# pwr.net
KiCad netlist of a schematic drawn in Altium Designer
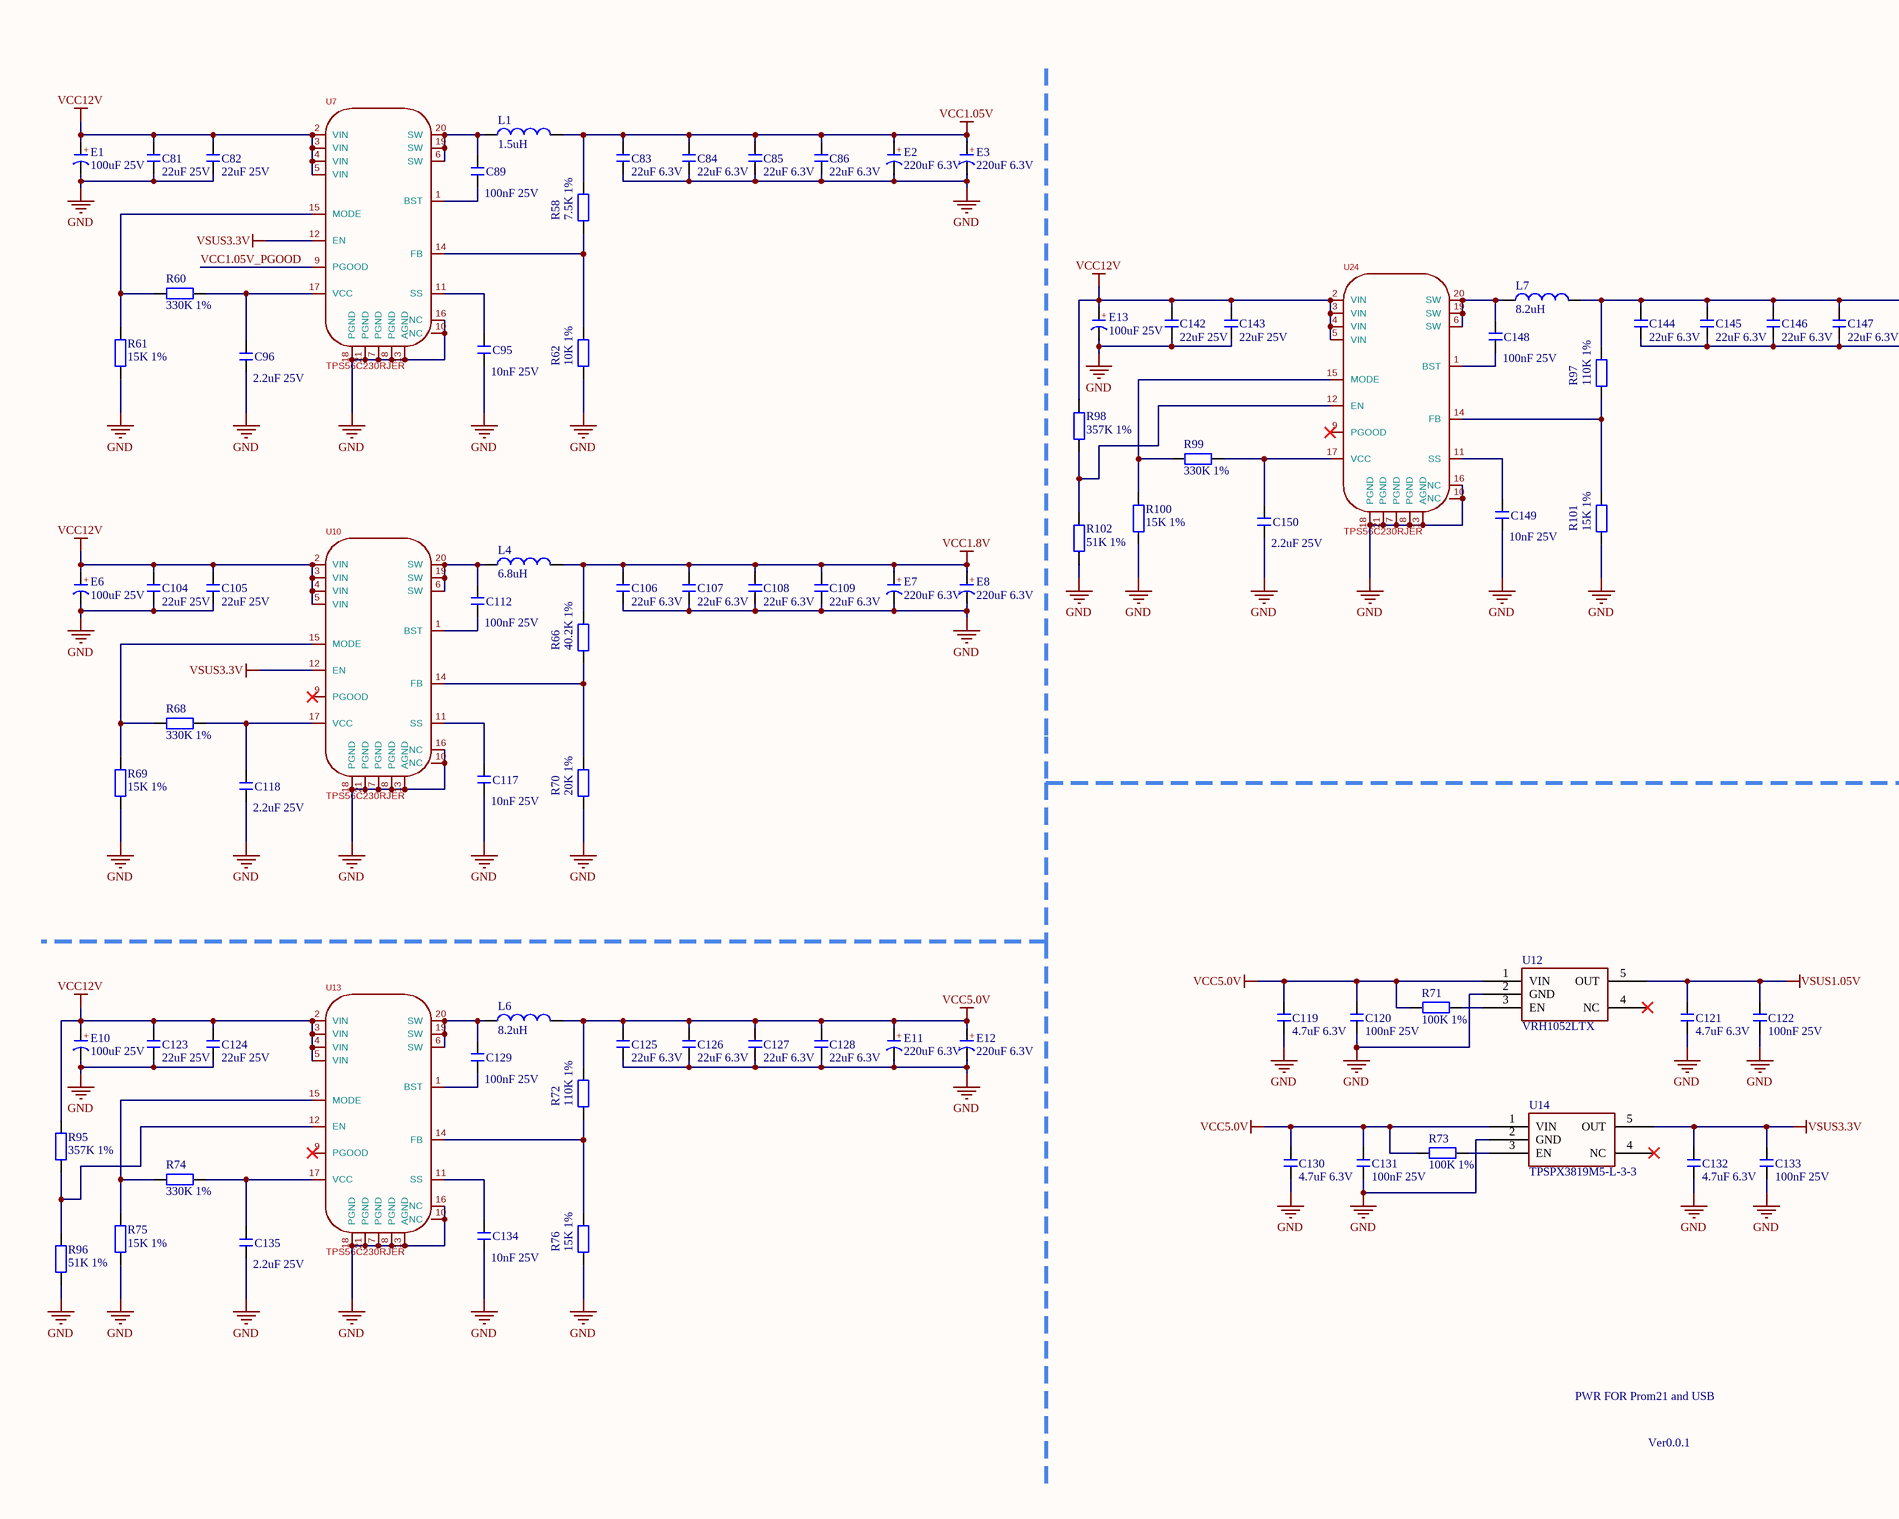
[diagram p0: pwr.SchDoc, left]
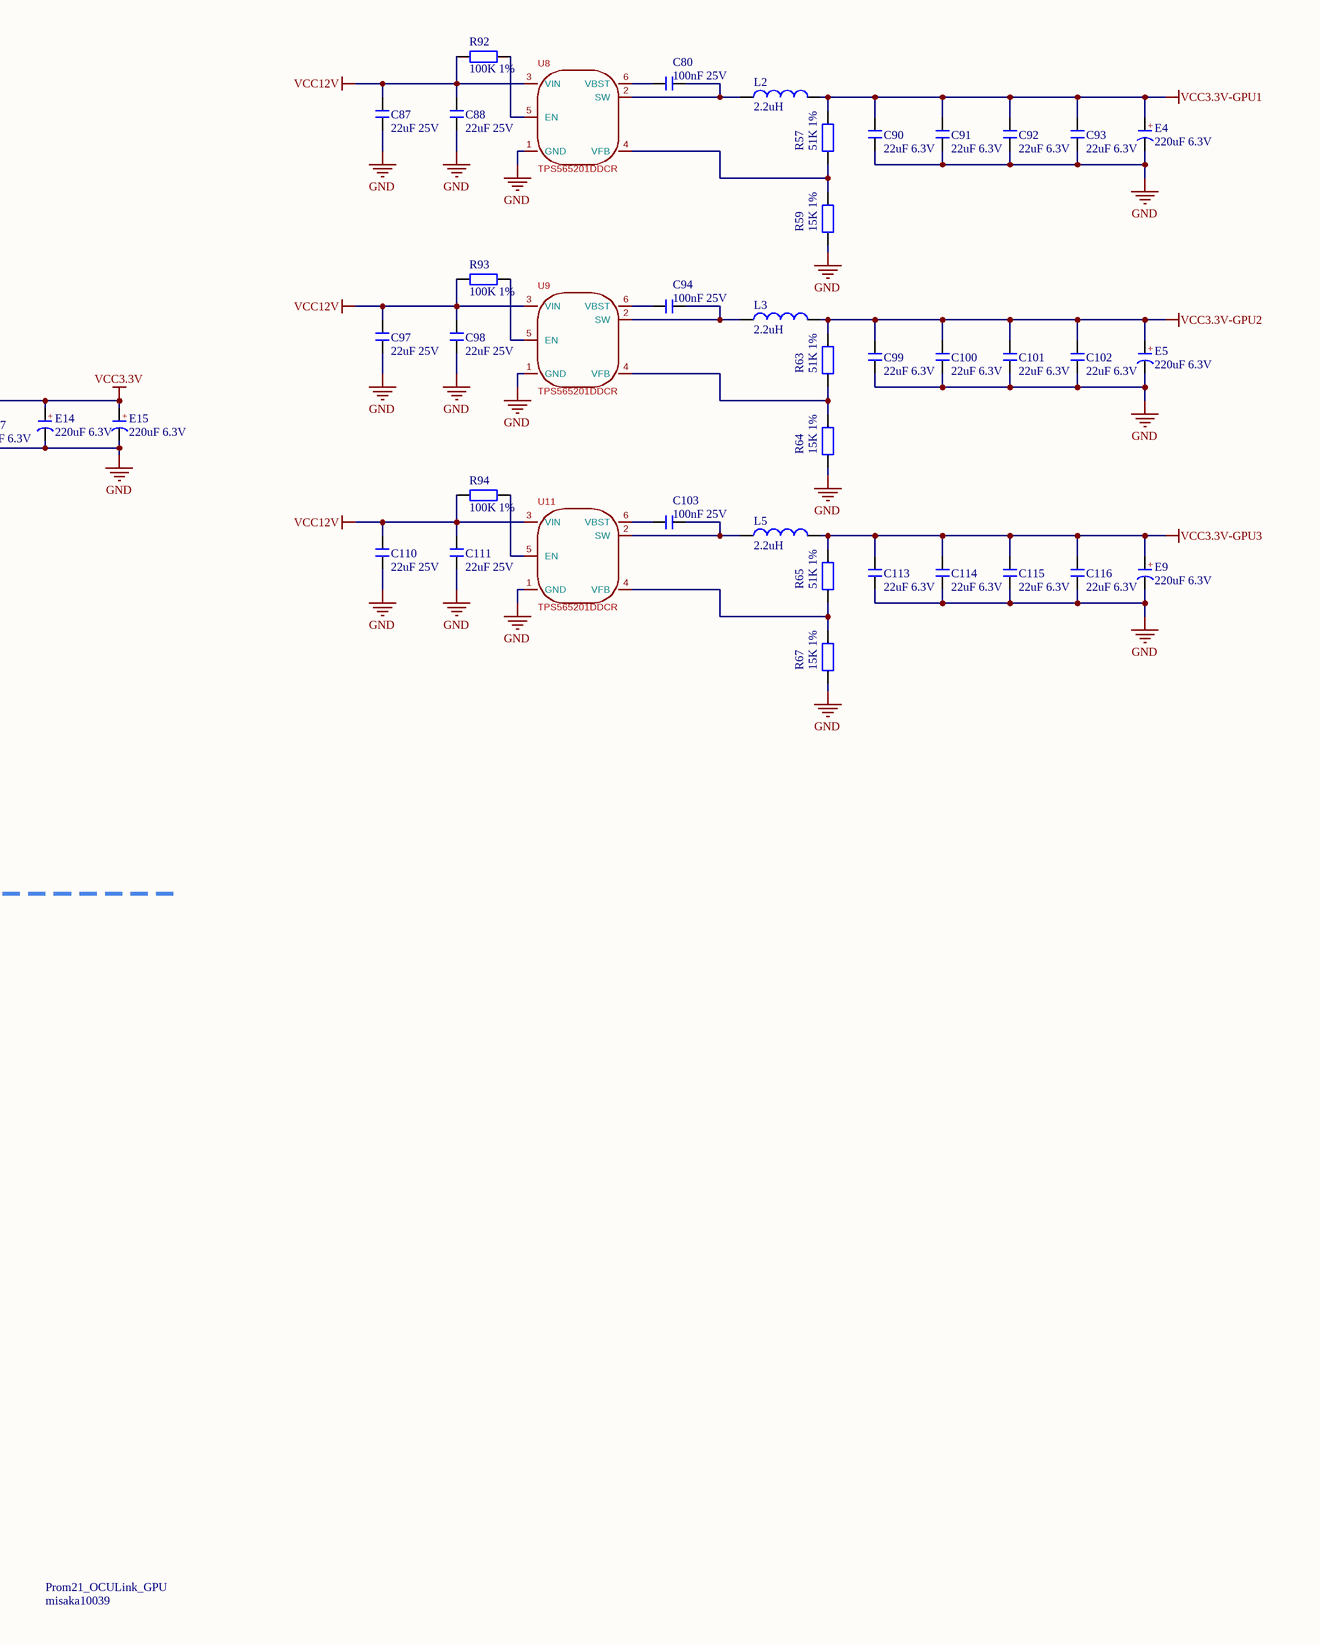
[diagram p1: pwr.SchDoc, right]

(export (version "E")
  (design (tool "Eeschema 10.0.6"))
  (components
    (comp (ref "C80")
      (value "100nF 25V")
      (footprint "C0402_L")
      (description "无极性贴片电容")
      (libsource (lib "Capacitor") (part "C"))
    )
    (comp (ref "C81")
      (value "22uF 25V")
      (footprint "C0805_L")
      (description "无极性贴片电容")
      (libsource (lib "Capacitor") (part "C"))
    )
    (comp (ref "C82")
      (value "22uF 25V")
      (footprint "C0805_L")
      (description "无极性贴片电容")
      (libsource (lib "Capacitor") (part "C"))
    )
    (comp (ref "C83")
      (value "22uF 6.3V")
      (footprint "C0603_L")
      (description "无极性贴片电容")
      (libsource (lib "Capacitor") (part "C"))
    )
    (comp (ref "C84")
      (value "22uF 6.3V")
      (footprint "C0603_L")
      (description "无极性贴片电容")
      (libsource (lib "Capacitor") (part "C"))
    )
    (comp (ref "C85")
      (value "22uF 6.3V")
      (footprint "C0603_L")
      (description "无极性贴片电容")
      (libsource (lib "Capacitor") (part "C"))
    )
    (comp (ref "C86")
      (value "22uF 6.3V")
      (footprint "C0603_L")
      (description "无极性贴片电容")
      (libsource (lib "Capacitor") (part "C"))
    )
    (comp (ref "C87")
      (value "22uF 25V")
      (footprint "C0805_L")
      (description "无极性贴片电容")
      (libsource (lib "Capacitor") (part "C"))
    )
    (comp (ref "C88")
      (value "22uF 25V")
      (footprint "C0805_L")
      (description "无极性贴片电容")
      (libsource (lib "Capacitor") (part "C"))
    )
    (comp (ref "C89")
      (value "100nF 25V")
      (footprint "C0402_L")
      (description "无极性贴片电容")
      (libsource (lib "Capacitor") (part "C"))
    )
    (comp (ref "C90")
      (value "22uF 6.3V")
      (footprint "C0603_L")
      (description "无极性贴片电容")
      (libsource (lib "Capacitor") (part "C"))
    )
    (comp (ref "C91")
      (value "22uF 6.3V")
      (footprint "C0603_L")
      (description "无极性贴片电容")
      (libsource (lib "Capacitor") (part "C"))
    )
    (comp (ref "C92")
      (value "22uF 6.3V")
      (footprint "C0603_L")
      (description "无极性贴片电容")
      (libsource (lib "Capacitor") (part "C"))
    )
    (comp (ref "C93")
      (value "22uF 6.3V")
      (footprint "C0603_L")
      (description "无极性贴片电容")
      (libsource (lib "Capacitor") (part "C"))
    )
    (comp (ref "C94")
      (value "100nF 25V")
      (footprint "C0402_L")
      (description "无极性贴片电容")
      (libsource (lib "Capacitor") (part "C"))
    )
    (comp (ref "C95")
      (value "10nF 25V")
      (footprint "C0402_L")
      (description "无极性贴片电容")
      (libsource (lib "Capacitor") (part "C"))
    )
    (comp (ref "C96")
      (value "2.2uF 25V")
      (footprint "C0402_L")
      (description "无极性贴片电容")
      (libsource (lib "Capacitor") (part "C"))
    )
    (comp (ref "C97")
      (value "22uF 25V")
      (footprint "C0805_L")
      (description "无极性贴片电容")
      (libsource (lib "Capacitor") (part "C"))
    )
    (comp (ref "C98")
      (value "22uF 25V")
      (footprint "C0805_L")
      (description "无极性贴片电容")
      (libsource (lib "Capacitor") (part "C"))
    )
    (comp (ref "C99")
      (value "22uF 6.3V")
      (footprint "C0603_L")
      (description "无极性贴片电容")
      (libsource (lib "Capacitor") (part "C"))
    )
    (comp (ref "C100")
      (value "22uF 6.3V")
      (footprint "C0603_L")
      (description "无极性贴片电容")
      (libsource (lib "Capacitor") (part "C"))
    )
    (comp (ref "C101")
      (value "22uF 6.3V")
      (footprint "C0603_L")
      (description "无极性贴片电容")
      (libsource (lib "Capacitor") (part "C"))
    )
    (comp (ref "C102")
      (value "22uF 6.3V")
      (footprint "C0603_L")
      (description "无极性贴片电容")
      (libsource (lib "Capacitor") (part "C"))
    )
    (comp (ref "C103")
      (value "100nF 25V")
      (footprint "C0402_L")
      (description "无极性贴片电容")
      (libsource (lib "Capacitor") (part "C"))
    )
    (comp (ref "C104")
      (value "22uF 25V")
      (footprint "C0805_L")
      (description "无极性贴片电容")
      (libsource (lib "Capacitor") (part "C"))
    )
    (comp (ref "C105")
      (value "22uF 25V")
      (footprint "C0805_L")
      (description "无极性贴片电容")
      (libsource (lib "Capacitor") (part "C"))
    )
    (comp (ref "C106")
      (value "22uF 6.3V")
      (footprint "C0603_L")
      (description "无极性贴片电容")
      (libsource (lib "Capacitor") (part "C"))
    )
    (comp (ref "C107")
      (value "22uF 6.3V")
      (footprint "C0603_L")
      (description "无极性贴片电容")
      (libsource (lib "Capacitor") (part "C"))
    )
    (comp (ref "C108")
      (value "22uF 6.3V")
      (footprint "C0603_L")
      (description "无极性贴片电容")
      (libsource (lib "Capacitor") (part "C"))
    )
    (comp (ref "C109")
      (value "22uF 6.3V")
      (footprint "C0603_L")
      (description "无极性贴片电容")
      (libsource (lib "Capacitor") (part "C"))
    )
    (comp (ref "C110")
      (value "22uF 25V")
      (footprint "C0805_L")
      (description "无极性贴片电容")
      (libsource (lib "Capacitor") (part "C"))
    )
    (comp (ref "C111")
      (value "22uF 25V")
      (footprint "C0805_L")
      (description "无极性贴片电容")
      (libsource (lib "Capacitor") (part "C"))
    )
    (comp (ref "C112")
      (value "100nF 25V")
      (footprint "C0402_L")
      (description "无极性贴片电容")
      (libsource (lib "Capacitor") (part "C"))
    )
    (comp (ref "C113")
      (value "22uF 6.3V")
      (footprint "C0603_L")
      (description "无极性贴片电容")
      (libsource (lib "Capacitor") (part "C"))
    )
    (comp (ref "C114")
      (value "22uF 6.3V")
      (footprint "C0603_L")
      (description "无极性贴片电容")
      (libsource (lib "Capacitor") (part "C"))
    )
    (comp (ref "C115")
      (value "22uF 6.3V")
      (footprint "C0603_L")
      (description "无极性贴片电容")
      (libsource (lib "Capacitor") (part "C"))
    )
    (comp (ref "C116")
      (value "22uF 6.3V")
      (footprint "C0603_L")
      (description "无极性贴片电容")
      (libsource (lib "Capacitor") (part "C"))
    )
    (comp (ref "C117")
      (value "10nF 25V")
      (footprint "C0402_L")
      (description "无极性贴片电容")
      (libsource (lib "Capacitor") (part "C"))
    )
    (comp (ref "C118")
      (value "2.2uF 25V")
      (footprint "C0402_L")
      (description "无极性贴片电容")
      (libsource (lib "Capacitor") (part "C"))
    )
    (comp (ref "C119")
      (value "4.7uF 6.3V")
      (footprint "C0402_L")
      (description "无极性贴片电容")
      (libsource (lib "Capacitor") (part "C"))
    )
    (comp (ref "C120")
      (value "100nF 25V")
      (footprint "C0402_L")
      (description "无极性贴片电容")
      (libsource (lib "Capacitor") (part "C"))
    )
    (comp (ref "C121")
      (value "4.7uF 6.3V")
      (footprint "C0402_L")
      (description "无极性贴片电容")
      (libsource (lib "Capacitor") (part "C"))
    )
    (comp (ref "C122")
      (value "100nF 25V")
      (footprint "C0402_L")
      (description "无极性贴片电容")
      (libsource (lib "Capacitor") (part "C"))
    )
    (comp (ref "C123")
      (value "22uF 25V")
      (footprint "C0805_L")
      (description "无极性贴片电容")
      (libsource (lib "Capacitor") (part "C"))
    )
    (comp (ref "C124")
      (value "22uF 25V")
      (footprint "C0805_L")
      (description "无极性贴片电容")
      (libsource (lib "Capacitor") (part "C"))
    )
    (comp (ref "C125")
      (value "22uF 6.3V")
      (footprint "C0603_L")
      (description "无极性贴片电容")
      (libsource (lib "Capacitor") (part "C"))
    )
    (comp (ref "C126")
      (value "22uF 6.3V")
      (footprint "C0603_L")
      (description "无极性贴片电容")
      (libsource (lib "Capacitor") (part "C"))
    )
    (comp (ref "C127")
      (value "22uF 6.3V")
      (footprint "C0603_L")
      (description "无极性贴片电容")
      (libsource (lib "Capacitor") (part "C"))
    )
    (comp (ref "C128")
      (value "22uF 6.3V")
      (footprint "C0603_L")
      (description "无极性贴片电容")
      (libsource (lib "Capacitor") (part "C"))
    )
    (comp (ref "C129")
      (value "100nF 25V")
      (footprint "C0402_L")
      (description "无极性贴片电容")
      (libsource (lib "Capacitor") (part "C"))
    )
    (comp (ref "C130")
      (value "4.7uF 6.3V")
      (footprint "C0402_L")
      (description "无极性贴片电容")
      (libsource (lib "Capacitor") (part "C"))
    )
    (comp (ref "C131")
      (value "100nF 25V")
      (footprint "C0402_L")
      (description "无极性贴片电容")
      (libsource (lib "Capacitor") (part "C"))
    )
    (comp (ref "C132")
      (value "4.7uF 6.3V")
      (footprint "C0402_L")
      (description "无极性贴片电容")
      (libsource (lib "Capacitor") (part "C"))
    )
    (comp (ref "C133")
      (value "100nF 25V")
      (footprint "C0402_L")
      (description "无极性贴片电容")
      (libsource (lib "Capacitor") (part "C"))
    )
    (comp (ref "C134")
      (value "10nF 25V")
      (footprint "C0402_L")
      (description "无极性贴片电容")
      (libsource (lib "Capacitor") (part "C"))
    )
    (comp (ref "C135")
      (value "2.2uF 25V")
      (footprint "C0402_L")
      (description "无极性贴片电容")
      (libsource (lib "Capacitor") (part "C"))
    )
    (comp (ref "C142")
      (value "22uF 25V")
      (footprint "C0805_L")
      (description "无极性贴片电容")
      (libsource (lib "Capacitor") (part "C"))
    )
    (comp (ref "C143")
      (value "22uF 25V")
      (footprint "C0805_L")
      (description "无极性贴片电容")
      (libsource (lib "Capacitor") (part "C"))
    )
    (comp (ref "C144")
      (value "22uF 6.3V")
      (footprint "C0603_L")
      (description "无极性贴片电容")
      (libsource (lib "Capacitor") (part "C"))
    )
    (comp (ref "C145")
      (value "22uF 6.3V")
      (footprint "C0603_L")
      (description "无极性贴片电容")
      (libsource (lib "Capacitor") (part "C"))
    )
    (comp (ref "C146")
      (value "22uF 6.3V")
      (footprint "C0603_L")
      (description "无极性贴片电容")
      (libsource (lib "Capacitor") (part "C"))
    )
    (comp (ref "C147")
      (value "22uF 6.3V")
      (footprint "C0603_L")
      (description "无极性贴片电容")
      (libsource (lib "Capacitor") (part "C"))
    )
    (comp (ref "C148")
      (value "100nF 25V")
      (footprint "C0402_L")
      (description "无极性贴片电容")
      (libsource (lib "Capacitor") (part "C"))
    )
    (comp (ref "C149")
      (value "10nF 25V")
      (footprint "C0402_L")
      (description "无极性贴片电容")
      (libsource (lib "Capacitor") (part "C"))
    )
    (comp (ref "C150")
      (value "2.2uF 25V")
      (footprint "C0402_L")
      (description "无极性贴片电容")
      (libsource (lib "Capacitor") (part "C"))
    )
    (comp (ref "E1")
      (value "100uF 25V")
      (footprint "CT 6*4 - R")
      (description "贴片电解电容")
      (libsource (lib "Capacitor") (part "C-CAP"))
    )
    (comp (ref "E2")
      (value "220uF 6.3V")
      (footprint "CT 6*4 - C")
      (description "贴片电解电容")
      (libsource (lib "Capacitor") (part "C-CAP"))
    )
    (comp (ref "E3")
      (value "220uF 6.3V")
      (footprint "CT 6*4 - C")
      (description "贴片电解电容")
      (libsource (lib "Capacitor") (part "C-CAP"))
    )
    (comp (ref "E4")
      (value "220uF 6.3V")
      (footprint "CT 6*4 - C")
      (description "贴片电解电容")
      (libsource (lib "Capacitor") (part "C-CAP"))
    )
    (comp (ref "E5")
      (value "220uF 6.3V")
      (footprint "CT 6*4 - C")
      (description "贴片电解电容")
      (libsource (lib "Capacitor") (part "C-CAP"))
    )
    (comp (ref "E6")
      (value "100uF 25V")
      (footprint "CT 6*4 - R")
      (description "贴片电解电容")
      (libsource (lib "Capacitor") (part "C-CAP"))
    )
    (comp (ref "E7")
      (value "220uF 6.3V")
      (footprint "CT 6*4 - C")
      (description "贴片电解电容")
      (libsource (lib "Capacitor") (part "C-CAP"))
    )
    (comp (ref "E8")
      (value "220uF 6.3V")
      (footprint "CT 6*4 - C")
      (description "贴片电解电容")
      (libsource (lib "Capacitor") (part "C-CAP"))
    )
    (comp (ref "E9")
      (value "220uF 6.3V")
      (footprint "CT 6*4 - C")
      (description "贴片电解电容")
      (libsource (lib "Capacitor") (part "C-CAP"))
    )
    (comp (ref "E10")
      (value "100uF 25V")
      (footprint "CT 6*4 - R")
      (description "贴片电解电容")
      (libsource (lib "Capacitor") (part "C-CAP"))
    )
    (comp (ref "E11")
      (value "220uF 6.3V")
      (footprint "CT 6*4 - C")
      (description "贴片电解电容")
      (libsource (lib "Capacitor") (part "C-CAP"))
    )
    (comp (ref "E12")
      (value "220uF 6.3V")
      (footprint "CT 6*4 - C")
      (description "贴片电解电容")
      (libsource (lib "Capacitor") (part "C-CAP"))
    )
    (comp (ref "E13")
      (value "100uF 25V")
      (footprint "CT 6*4 - R")
      (description "贴片电解电容")
      (libsource (lib "Capacitor") (part "C-CAP"))
    )
    (comp (ref "E14")
      (value "220uF 6.3V")
      (footprint "CT 6*4 - C")
      (description "贴片电解电容")
      (libsource (lib "Capacitor") (part "C-CAP"))
    )
    (comp (ref "E15")
      (value "220uF 6.3V")
      (footprint "CT 6*4 - C")
      (description "贴片电解电容")
      (libsource (lib "Capacitor") (part "C-CAP"))
    )
    (comp (ref "L1")
      (value "1.5uH")
      (footprint "L0630贴片电感")
      (description "小功率贴片电感")
      (libsource (lib "Inductor") (part "L"))
    )
    (comp (ref "L2")
      (value "2.2uH")
      (footprint "L0630贴片电感")
      (description "小功率贴片电感")
      (libsource (lib "Inductor") (part "L"))
    )
    (comp (ref "L3")
      (value "2.2uH")
      (footprint "L0630贴片电感")
      (description "小功率贴片电感")
      (libsource (lib "Inductor") (part "L"))
    )
    (comp (ref "L4")
      (value "6.8uH")
      (footprint "L0630贴片电感")
      (description "小功率贴片电感")
      (libsource (lib "Inductor") (part "L"))
    )
    (comp (ref "L5")
      (value "2.2uH")
      (footprint "L0630贴片电感")
      (description "小功率贴片电感")
      (libsource (lib "Inductor") (part "L"))
    )
    (comp (ref "L6")
      (value "8.2uH")
      (footprint "L0630贴片电感")
      (description "小功率贴片电感")
      (libsource (lib "Inductor") (part "L"))
    )
    (comp (ref "L7")
      (value "8.2uH")
      (footprint "L0630贴片电感")
      (description "小功率贴片电感")
      (libsource (lib "Inductor") (part "L"))
    )
    (comp (ref "R57")
      (value "51K 1%")
      (footprint "R0402_L")
      (description "贴片电阻")
      (libsource (lib "Resistor") (part "R"))
    )
    (comp (ref "R58")
      (value "7.5K 1%")
      (footprint "R0402_L")
      (description "贴片电阻")
      (libsource (lib "Resistor") (part "R"))
    )
    (comp (ref "R59")
      (value "15K 1%")
      (footprint "R0402_L")
      (description "贴片电阻")
      (libsource (lib "Resistor") (part "R"))
    )
    (comp (ref "R60")
      (value "330K 1%")
      (footprint "R0402_L")
      (description "贴片电阻")
      (libsource (lib "Resistor") (part "R"))
    )
    (comp (ref "R61")
      (value "15K 1%")
      (footprint "R0402_L")
      (description "贴片电阻")
      (libsource (lib "Resistor") (part "R"))
    )
    (comp (ref "R62")
      (value "10K 1%")
      (footprint "R0402_L")
      (description "贴片电阻")
      (libsource (lib "Resistor") (part "R"))
    )
    (comp (ref "R63")
      (value "51K 1%")
      (footprint "R0402_L")
      (description "贴片电阻")
      (libsource (lib "Resistor") (part "R"))
    )
    (comp (ref "R64")
      (value "15K 1%")
      (footprint "R0402_L")
      (description "贴片电阻")
      (libsource (lib "Resistor") (part "R"))
    )
    (comp (ref "R65")
      (value "51K 1%")
      (footprint "R0402_L")
      (description "贴片电阻")
      (libsource (lib "Resistor") (part "R"))
    )
    (comp (ref "R66")
      (value "40.2K 1%")
      (footprint "R0402_L")
      (description "贴片电阻")
      (libsource (lib "Resistor") (part "R"))
    )
    (comp (ref "R67")
      (value "15K 1%")
      (footprint "R0402_L")
      (description "贴片电阻")
      (libsource (lib "Resistor") (part "R"))
    )
    (comp (ref "R68")
      (value "330K 1%")
      (footprint "R0402_L")
      (description "贴片电阻")
      (libsource (lib "Resistor") (part "R"))
    )
    (comp (ref "R69")
      (value "15K 1%")
      (footprint "R0402_L")
      (description "贴片电阻")
      (libsource (lib "Resistor") (part "R"))
    )
    (comp (ref "R70")
      (value "20K 1%")
      (footprint "R0402_L")
      (description "贴片电阻")
      (libsource (lib "Resistor") (part "R"))
    )
    (comp (ref "R71")
      (value "100K 1%")
      (footprint "R0402_L")
      (description "贴片电阻")
      (libsource (lib "Resistor") (part "R"))
    )
    (comp (ref "R72")
      (value "110K 1%")
      (footprint "R0402_L")
      (description "贴片电阻")
      (libsource (lib "Resistor") (part "R"))
    )
    (comp (ref "R73")
      (value "100K 1%")
      (footprint "R0402_L")
      (description "贴片电阻")
      (libsource (lib "Resistor") (part "R"))
    )
    (comp (ref "R74")
      (value "330K 1%")
      (footprint "R0402_L")
      (description "贴片电阻")
      (libsource (lib "Resistor") (part "R"))
    )
    (comp (ref "R75")
      (value "15K 1%")
      (footprint "R0402_L")
      (description "贴片电阻")
      (libsource (lib "Resistor") (part "R"))
    )
    (comp (ref "R76")
      (value "15K 1%")
      (footprint "R0402_L")
      (description "贴片电阻")
      (libsource (lib "Resistor") (part "R"))
    )
    (comp (ref "R92")
      (value "100K 1%")
      (footprint "R0402_L")
      (description "贴片电阻")
      (libsource (lib "Resistor") (part "R"))
    )
    (comp (ref "R93")
      (value "100K 1%")
      (footprint "R0402_L")
      (description "贴片电阻")
      (libsource (lib "Resistor") (part "R"))
    )
    (comp (ref "R94")
      (value "100K 1%")
      (footprint "R0402_L")
      (description "贴片电阻")
      (libsource (lib "Resistor") (part "R"))
    )
    (comp (ref "R95")
      (value "357K 1%")
      (footprint "R0402_L")
      (description "贴片电阻")
      (libsource (lib "Resistor") (part "R"))
    )
    (comp (ref "R96")
      (value "51K 1%")
      (footprint "R0402_L")
      (description "贴片电阻")
      (libsource (lib "Resistor") (part "R"))
    )
    (comp (ref "R97")
      (value "110K 1%")
      (footprint "R0402_L")
      (description "贴片电阻")
      (libsource (lib "Resistor") (part "R"))
    )
    (comp (ref "R98")
      (value "357K 1%")
      (footprint "R0402_L")
      (description "贴片电阻")
      (libsource (lib "Resistor") (part "R"))
    )
    (comp (ref "R99")
      (value "330K 1%")
      (footprint "R0402_L")
      (description "贴片电阻")
      (libsource (lib "Resistor") (part "R"))
    )
    (comp (ref "R100")
      (value "15K 1%")
      (footprint "R0402_L")
      (description "贴片电阻")
      (libsource (lib "Resistor") (part "R"))
    )
    (comp (ref "R101")
      (value "15K 1%")
      (footprint "R0402_L")
      (description "贴片电阻")
      (libsource (lib "Resistor") (part "R"))
    )
    (comp (ref "R102")
      (value "51K 1%")
      (footprint "R0402_L")
      (description "贴片电阻")
      (libsource (lib "Resistor") (part "R"))
    )
    (comp (ref "U7")
      (value "TPS56C230RJER")
      (footprint "VQFN-20_L3.0-W3.0-P0.45-TL-EP_TI_RJE")
      (description "功能类型:降压型;输出类型:可调;输入电压:4.5V~18V;输出电压:600mV~5.5V;输出电流(最大值):12A;")
      (fields (field (name "MANUFACTURER") "TI(德州仪器)"))
      (libsource (lib "DCDC Convert") (part "TPS56C230RJER"))
    )
    (comp (ref "U8")
      (value "TPS565201DDCR")
      (footprint "SOT23-6L")
      (description "功能类型:降压型;输出类型:可调;输入电压:4.5V~17V;输出电压:600mV~7V;输出电流(最大值):5A;")
      (fields (field (name "MANUFACTURER") "TI(德州仪器)"))
      (libsource (lib "DCDC Convert") (part "TPS565201DDCR"))
    )
    (comp (ref "U9")
      (value "TPS565201DDCR")
      (footprint "SOT23-6L")
      (description "功能类型:降压型;输出类型:可调;输入电压:4.5V~17V;输出电压:600mV~7V;输出电流(最大值):5A;")
      (fields (field (name "MANUFACTURER") "TI(德州仪器)"))
      (libsource (lib "DCDC Convert") (part "TPS565201DDCR"))
    )
    (comp (ref "U10")
      (value "TPS56C230RJER")
      (footprint "VQFN-20_L3.0-W3.0-P0.45-TL-EP_TI_RJE")
      (description "功能类型:降压型;输出类型:可调;输入电压:4.5V~18V;输出电压:600mV~5.5V;输出电流(最大值):12A;")
      (fields (field (name "MANUFACTURER") "TI(德州仪器)"))
      (libsource (lib "DCDC Convert") (part "TPS56C230RJER"))
    )
    (comp (ref "U11")
      (value "TPS565201DDCR")
      (footprint "SOT23-6L")
      (description "功能类型:降压型;输出类型:可调;输入电压:4.5V~17V;输出电压:600mV~7V;输出电流(最大值):5A;")
      (fields (field (name "MANUFACTURER") "TI(德州仪器)"))
      (libsource (lib "DCDC Convert") (part "TPS565201DDCR"))
    )
    (comp (ref "U12")
      (value "VRH1052LTX")
      (footprint "SOT23-5L")
      (description "SOT-23-5")
      (libsource (lib "LDO") (part "LP5907_MFX"))
    )
    (comp (ref "U13")
      (value "TPS56C230RJER")
      (footprint "VQFN-20_L3.0-W3.0-P0.45-TL-EP_TI_RJE")
      (description "功能类型:降压型;输出类型:可调;输入电压:4.5V~18V;输出电压:600mV~5.5V;输出电流(最大值):12A;")
      (fields (field (name "MANUFACTURER") "TI(德州仪器)"))
      (libsource (lib "DCDC Convert") (part "TPS56C230RJER"))
    )
    (comp (ref "U14")
      (value "TPSPX3819M5-L-3-3")
      (footprint "SOT23-5L")
      (description "SOT-23-5")
      (libsource (lib "LDO") (part "LP5907_MFX"))
    )
    (comp (ref "U24")
      (value "TPS56C230RJER")
      (footprint "VQFN-20_L3.0-W3.0-P0.45-TL-EP_TI_RJE")
      (description "功能类型:降压型;输出类型:可调;输入电压:4.5V~18V;输出电压:600mV~5.5V;输出电流(最大值):12A;")
      (fields (field (name "MANUFACTURER") "TI(德州仪器)"))
      (libsource (lib "DCDC Convert") (part "TPS56C230RJER"))
    )
  )
  (nets
    (net (code "1") (name "/VCC1.05V_PGOOD") (class "Default")
      (node (ref "U7") (pin "9") (pinfunction "PGOOD_9") (pintype "passive"))
    )
    (net (code "2") (name "GND") (class "Default")
      (node (ref "C100") (pin "1") (pinfunction "1_1") (pintype "passive"))
      (node (ref "C101") (pin "1") (pinfunction "1_1") (pintype "passive"))
      (node (ref "C102") (pin "1") (pinfunction "1_1") (pintype "passive"))
      (node (ref "C104") (pin "1") (pinfunction "1_1") (pintype "passive"))
      (node (ref "C105") (pin "1") (pinfunction "1_1") (pintype "passive"))
      (node (ref "C106") (pin "1") (pinfunction "1_1") (pintype "passive"))
      (node (ref "C107") (pin "1") (pinfunction "1_1") (pintype "passive"))
      (node (ref "C108") (pin "1") (pinfunction "1_1") (pintype "passive"))
      (node (ref "C109") (pin "1") (pinfunction "1_1") (pintype "passive"))
      (node (ref "C110") (pin "1") (pinfunction "1_1") (pintype "passive"))
      (node (ref "C111") (pin "1") (pinfunction "1_1") (pintype "passive"))
      (node (ref "C113") (pin "1") (pinfunction "1_1") (pintype "passive"))
      (node (ref "C114") (pin "1") (pinfunction "1_1") (pintype "passive"))
      (node (ref "C115") (pin "1") (pinfunction "1_1") (pintype "passive"))
      (node (ref "C116") (pin "1") (pinfunction "1_1") (pintype "passive"))
      (node (ref "C117") (pin "1") (pinfunction "1_1") (pintype "passive"))
      (node (ref "C118") (pin "1") (pinfunction "1_1") (pintype "passive"))
      (node (ref "C119") (pin "1") (pinfunction "1_1") (pintype "passive"))
      (node (ref "C120") (pin "2") (pinfunction "2_2") (pintype "passive"))
      (node (ref "C121") (pin "1") (pinfunction "1_1") (pintype "passive"))
      (node (ref "C122") (pin "2") (pinfunction "2_2") (pintype "passive"))
      (node (ref "C123") (pin "1") (pinfunction "1_1") (pintype "passive"))
      (node (ref "C124") (pin "1") (pinfunction "1_1") (pintype "passive"))
      (node (ref "C125") (pin "1") (pinfunction "1_1") (pintype "passive"))
      (node (ref "C126") (pin "1") (pinfunction "1_1") (pintype "passive"))
      (node (ref "C127") (pin "1") (pinfunction "1_1") (pintype "passive"))
      (node (ref "C128") (pin "1") (pinfunction "1_1") (pintype "passive"))
      (node (ref "C130") (pin "1") (pinfunction "1_1") (pintype "passive"))
      (node (ref "C131") (pin "2") (pinfunction "2_2") (pintype "passive"))
      (node (ref "C132") (pin "1") (pinfunction "1_1") (pintype "passive"))
      (node (ref "C133") (pin "2") (pinfunction "2_2") (pintype "passive"))
      (node (ref "C134") (pin "1") (pinfunction "1_1") (pintype "passive"))
      (node (ref "C135") (pin "1") (pinfunction "1_1") (pintype "passive"))
      (node (ref "C142") (pin "1") (pinfunction "1_1") (pintype "passive"))
      (node (ref "C143") (pin "1") (pinfunction "1_1") (pintype "passive"))
      (node (ref "C144") (pin "1") (pinfunction "1_1") (pintype "passive"))
      (node (ref "C145") (pin "1") (pinfunction "1_1") (pintype "passive"))
      (node (ref "C146") (pin "1") (pinfunction "1_1") (pintype "passive"))
      (node (ref "C147") (pin "1") (pinfunction "1_1") (pintype "passive"))
      (node (ref "C149") (pin "1") (pinfunction "1_1") (pintype "passive"))
      (node (ref "C150") (pin "1") (pinfunction "1_1") (pintype "passive"))
      (node (ref "C81") (pin "1") (pinfunction "1_1") (pintype "passive"))
      (node (ref "C82") (pin "1") (pinfunction "1_1") (pintype "passive"))
      (node (ref "C83") (pin "1") (pinfunction "1_1") (pintype "passive"))
      (node (ref "C84") (pin "1") (pinfunction "1_1") (pintype "passive"))
      (node (ref "C85") (pin "1") (pinfunction "1_1") (pintype "passive"))
      (node (ref "C86") (pin "1") (pinfunction "1_1") (pintype "passive"))
      (node (ref "C87") (pin "1") (pinfunction "1_1") (pintype "passive"))
      (node (ref "C88") (pin "1") (pinfunction "1_1") (pintype "passive"))
      (node (ref "C90") (pin "1") (pinfunction "1_1") (pintype "passive"))
      (node (ref "C91") (pin "1") (pinfunction "1_1") (pintype "passive"))
      (node (ref "C92") (pin "1") (pinfunction "1_1") (pintype "passive"))
      (node (ref "C93") (pin "1") (pinfunction "1_1") (pintype "passive"))
      (node (ref "C95") (pin "1") (pinfunction "1_1") (pintype "passive"))
      (node (ref "C96") (pin "1") (pinfunction "1_1") (pintype "passive"))
      (node (ref "C97") (pin "1") (pinfunction "1_1") (pintype "passive"))
      (node (ref "C98") (pin "1") (pinfunction "1_1") (pintype "passive"))
      (node (ref "C99") (pin "1") (pinfunction "1_1") (pintype "passive"))
      (node (ref "E1") (pin "2") (pinfunction "K_2") (pintype "passive"))
      (node (ref "E10") (pin "2") (pinfunction "K_2") (pintype "passive"))
      (node (ref "E11") (pin "2") (pinfunction "K_2") (pintype "passive"))
      (node (ref "E12") (pin "2") (pinfunction "K_2") (pintype "passive"))
      (node (ref "E13") (pin "2") (pinfunction "K_2") (pintype "passive"))
      (node (ref "E14") (pin "2") (pinfunction "K_2") (pintype "passive"))
      (node (ref "E15") (pin "2") (pinfunction "K_2") (pintype "passive"))
      (node (ref "E2") (pin "2") (pinfunction "K_2") (pintype "passive"))
      (node (ref "E3") (pin "2") (pinfunction "K_2") (pintype "passive"))
      (node (ref "E4") (pin "2") (pinfunction "K_2") (pintype "passive"))
      (node (ref "E5") (pin "2") (pinfunction "K_2") (pintype "passive"))
      (node (ref "E6") (pin "2") (pinfunction "K_2") (pintype "passive"))
      (node (ref "E7") (pin "2") (pinfunction "K_2") (pintype "passive"))
      (node (ref "E8") (pin "2") (pinfunction "K_2") (pintype "passive"))
      (node (ref "E9") (pin "2") (pinfunction "K_2") (pintype "passive"))
      (node (ref "R100") (pin "1") (pinfunction "1_1") (pintype "passive"))
      (node (ref "R101") (pin "2") (pinfunction "2_2") (pintype "passive"))
      (node (ref "R102") (pin "1") (pinfunction "1_1") (pintype "passive"))
      (node (ref "R59") (pin "2") (pinfunction "2_2") (pintype "passive"))
      (node (ref "R61") (pin "1") (pinfunction "1_1") (pintype "passive"))
      (node (ref "R62") (pin "2") (pinfunction "2_2") (pintype "passive"))
      (node (ref "R64") (pin "2") (pinfunction "2_2") (pintype "passive"))
      (node (ref "R67") (pin "2") (pinfunction "2_2") (pintype "passive"))
      (node (ref "R69") (pin "1") (pinfunction "1_1") (pintype "passive"))
      (node (ref "R70") (pin "2") (pinfunction "2_2") (pintype "passive"))
      (node (ref "R75") (pin "1") (pinfunction "1_1") (pintype "passive"))
      (node (ref "R76") (pin "2") (pinfunction "2_2") (pintype "passive"))
      (node (ref "R96") (pin "1") (pinfunction "1_1") (pintype "passive"))
      (node (ref "U10") (pin "10") (pinfunction "NC_10") (pintype "passive"))
      (node (ref "U10") (pin "13") (pinfunction "AGND_13") (pintype "passive"))
      (node (ref "U10") (pin "16") (pinfunction "NC_16") (pintype "passive"))
      (node (ref "U10") (pin "18") (pinfunction "PGND_18") (pintype "passive"))
      (node (ref "U10") (pin "21") (pinfunction "PGND_21") (pintype "passive"))
      (node (ref "U10") (pin "7") (pinfunction "PGND_7") (pintype "passive"))
      (node (ref "U10") (pin "8") (pinfunction "PGND_8") (pintype "passive"))
      (node (ref "U11") (pin "1") (pinfunction "GND_1") (pintype "passive"))
      (node (ref "U12") (pin "2") (pinfunction "GND_2") (pintype "passive"))
      (node (ref "U13") (pin "10") (pinfunction "NC_10") (pintype "passive"))
      (node (ref "U13") (pin "13") (pinfunction "AGND_13") (pintype "passive"))
      (node (ref "U13") (pin "16") (pinfunction "NC_16") (pintype "passive"))
      (node (ref "U13") (pin "18") (pinfunction "PGND_18") (pintype "passive"))
      (node (ref "U13") (pin "21") (pinfunction "PGND_21") (pintype "passive"))
      (node (ref "U13") (pin "7") (pinfunction "PGND_7") (pintype "passive"))
      (node (ref "U13") (pin "8") (pinfunction "PGND_8") (pintype "passive"))
      (node (ref "U14") (pin "2") (pinfunction "GND_2") (pintype "passive"))
      (node (ref "U24") (pin "10") (pinfunction "NC_10") (pintype "passive"))
      (node (ref "U24") (pin "13") (pinfunction "AGND_13") (pintype "passive"))
      (node (ref "U24") (pin "16") (pinfunction "NC_16") (pintype "passive"))
      (node (ref "U24") (pin "18") (pinfunction "PGND_18") (pintype "passive"))
      (node (ref "U24") (pin "21") (pinfunction "PGND_21") (pintype "passive"))
      (node (ref "U24") (pin "7") (pinfunction "PGND_7") (pintype "passive"))
      (node (ref "U24") (pin "8") (pinfunction "PGND_8") (pintype "passive"))
      (node (ref "U7") (pin "10") (pinfunction "NC_10") (pintype "passive"))
      (node (ref "U7") (pin "13") (pinfunction "AGND_13") (pintype "passive"))
      (node (ref "U7") (pin "16") (pinfunction "NC_16") (pintype "passive"))
      (node (ref "U7") (pin "18") (pinfunction "PGND_18") (pintype "passive"))
      (node (ref "U7") (pin "21") (pinfunction "PGND_21") (pintype "passive"))
      (node (ref "U7") (pin "7") (pinfunction "PGND_7") (pintype "passive"))
      (node (ref "U7") (pin "8") (pinfunction "PGND_8") (pintype "passive"))
      (node (ref "U8") (pin "1") (pinfunction "GND_1") (pintype "passive"))
      (node (ref "U9") (pin "1") (pinfunction "GND_1") (pintype "passive"))
    )
    (net (code "3") (name "Net-(C89-Pad2)") (class "Default")
      (node (ref "C89") (pin "2") (pinfunction "2_2") (pintype "passive"))
      (node (ref "L1") (pin "1") (pinfunction "1_1") (pintype "passive"))
      (node (ref "U7") (pin "19") (pinfunction "SW_19") (pintype "passive"))
      (node (ref "U7") (pin "20") (pinfunction "SW_20") (pintype "passive"))
      (node (ref "U7") (pin "6") (pinfunction "SW_6") (pintype "passive"))
    )
    (net (code "4") (name "Net-(C112-Pad2)") (class "Default")
      (node (ref "C112") (pin "2") (pinfunction "2_2") (pintype "passive"))
      (node (ref "L4") (pin "1") (pinfunction "1_1") (pintype "passive"))
      (node (ref "U10") (pin "19") (pinfunction "SW_19") (pintype "passive"))
      (node (ref "U10") (pin "20") (pinfunction "SW_20") (pintype "passive"))
      (node (ref "U10") (pin "6") (pinfunction "SW_6") (pintype "passive"))
    )
    (net (code "5") (name "Net-(C129-Pad2)") (class "Default")
      (node (ref "C129") (pin "2") (pinfunction "2_2") (pintype "passive"))
      (node (ref "L6") (pin "1") (pinfunction "1_1") (pintype "passive"))
      (node (ref "U13") (pin "19") (pinfunction "SW_19") (pintype "passive"))
      (node (ref "U13") (pin "20") (pinfunction "SW_20") (pintype "passive"))
      (node (ref "U13") (pin "6") (pinfunction "SW_6") (pintype "passive"))
    )
    (net (code "6") (name "Net-(C148-Pad2)") (class "Default")
      (node (ref "C148") (pin "2") (pinfunction "2_2") (pintype "passive"))
      (node (ref "L7") (pin "1") (pinfunction "1_1") (pintype "passive"))
      (node (ref "U24") (pin "19") (pinfunction "SW_19") (pintype "passive"))
      (node (ref "U24") (pin "20") (pinfunction "SW_20") (pintype "passive"))
      (node (ref "U24") (pin "6") (pinfunction "SW_6") (pintype "passive"))
    )
    (net (code "7") (name "Net-(U7-BST)") (class "Default")
      (node (ref "C89") (pin "1") (pinfunction "1_1") (pintype "passive"))
      (node (ref "U7") (pin "1") (pinfunction "BST_1") (pintype "passive"))
    )
    (net (code "8") (name "Net-(U7-FB)") (class "Default")
      (node (ref "R58") (pin "2") (pinfunction "2_2") (pintype "passive"))
      (node (ref "R62") (pin "1") (pinfunction "1_1") (pintype "passive"))
      (node (ref "U7") (pin "14") (pinfunction "FB_14") (pintype "passive"))
    )
    (net (code "9") (name "Net-(U7-MODE)") (class "Default")
      (node (ref "R60") (pin "2") (pinfunction "2_2") (pintype "passive"))
      (node (ref "R61") (pin "2") (pinfunction "2_2") (pintype "passive"))
      (node (ref "U7") (pin "15") (pinfunction "MODE_15") (pintype "passive"))
    )
    (net (code "10") (name "Net-(U7-SS)") (class "Default")
      (node (ref "C95") (pin "2") (pinfunction "2_2") (pintype "passive"))
      (node (ref "U7") (pin "11") (pinfunction "SS_11") (pintype "passive"))
    )
    (net (code "11") (name "Net-(U7-VCC)") (class "Default")
      (node (ref "C96") (pin "2") (pinfunction "2_2") (pintype "passive"))
      (node (ref "R60") (pin "1") (pinfunction "1_1") (pintype "passive"))
      (node (ref "U7") (pin "17") (pinfunction "VCC_17") (pintype "passive"))
    )
    (net (code "12") (name "Net-(U8-EN)") (class "Default")
      (node (ref "R92") (pin "2") (pinfunction "2_2") (pintype "passive"))
      (node (ref "U8") (pin "5") (pinfunction "EN_5") (pintype "passive"))
    )
    (net (code "13") (name "Net-(U8-SW)") (class "Default")
      (node (ref "C80") (pin "1") (pinfunction "1_1") (pintype "passive"))
      (node (ref "L2") (pin "1") (pinfunction "1_1") (pintype "passive"))
      (node (ref "U8") (pin "2") (pinfunction "SW_2") (pintype "passive"))
    )
    (net (code "14") (name "Net-(U8-VBST)") (class "Default")
      (node (ref "C80") (pin "2") (pinfunction "2_2") (pintype "passive"))
      (node (ref "U8") (pin "6") (pinfunction "VBST_6") (pintype "passive"))
    )
    (net (code "15") (name "Net-(U8-VFB)") (class "Default")
      (node (ref "R57") (pin "2") (pinfunction "2_2") (pintype "passive"))
      (node (ref "R59") (pin "1") (pinfunction "1_1") (pintype "passive"))
      (node (ref "U8") (pin "4") (pinfunction "VFB_4") (pintype "passive"))
    )
    (net (code "16") (name "Net-(U9-EN)") (class "Default")
      (node (ref "R93") (pin "2") (pinfunction "2_2") (pintype "passive"))
      (node (ref "U9") (pin "5") (pinfunction "EN_5") (pintype "passive"))
    )
    (net (code "17") (name "Net-(U9-SW)") (class "Default")
      (node (ref "C94") (pin "1") (pinfunction "1_1") (pintype "passive"))
      (node (ref "L3") (pin "1") (pinfunction "1_1") (pintype "passive"))
      (node (ref "U9") (pin "2") (pinfunction "SW_2") (pintype "passive"))
    )
    (net (code "18") (name "Net-(U9-VBST)") (class "Default")
      (node (ref "C94") (pin "2") (pinfunction "2_2") (pintype "passive"))
      (node (ref "U9") (pin "6") (pinfunction "VBST_6") (pintype "passive"))
    )
    (net (code "19") (name "Net-(U9-VFB)") (class "Default")
      (node (ref "R63") (pin "2") (pinfunction "2_2") (pintype "passive"))
      (node (ref "R64") (pin "1") (pinfunction "1_1") (pintype "passive"))
      (node (ref "U9") (pin "4") (pinfunction "VFB_4") (pintype "passive"))
    )
    (net (code "20") (name "Net-(U10-BST)") (class "Default")
      (node (ref "C112") (pin "1") (pinfunction "1_1") (pintype "passive"))
      (node (ref "U10") (pin "1") (pinfunction "BST_1") (pintype "passive"))
    )
    (net (code "21") (name "Net-(U10-FB)") (class "Default")
      (node (ref "R66") (pin "2") (pinfunction "2_2") (pintype "passive"))
      (node (ref "R70") (pin "1") (pinfunction "1_1") (pintype "passive"))
      (node (ref "U10") (pin "14") (pinfunction "FB_14") (pintype "passive"))
    )
    (net (code "22") (name "Net-(U10-MODE)") (class "Default")
      (node (ref "R68") (pin "2") (pinfunction "2_2") (pintype "passive"))
      (node (ref "R69") (pin "2") (pinfunction "2_2") (pintype "passive"))
      (node (ref "U10") (pin "15") (pinfunction "MODE_15") (pintype "passive"))
    )
    (net (code "23") (name "Net-(U10-SS)") (class "Default")
      (node (ref "C117") (pin "2") (pinfunction "2_2") (pintype "passive"))
      (node (ref "U10") (pin "11") (pinfunction "SS_11") (pintype "passive"))
    )
    (net (code "24") (name "Net-(U10-VCC)") (class "Default")
      (node (ref "C118") (pin "2") (pinfunction "2_2") (pintype "passive"))
      (node (ref "R68") (pin "1") (pinfunction "1_1") (pintype "passive"))
      (node (ref "U10") (pin "17") (pinfunction "VCC_17") (pintype "passive"))
    )
    (net (code "25") (name "Net-(U11-EN)") (class "Default")
      (node (ref "R94") (pin "2") (pinfunction "2_2") (pintype "passive"))
      (node (ref "U11") (pin "5") (pinfunction "EN_5") (pintype "passive"))
    )
    (net (code "26") (name "Net-(U11-SW)") (class "Default")
      (node (ref "C103") (pin "1") (pinfunction "1_1") (pintype "passive"))
      (node (ref "L5") (pin "1") (pinfunction "1_1") (pintype "passive"))
      (node (ref "U11") (pin "2") (pinfunction "SW_2") (pintype "passive"))
    )
    (net (code "27") (name "Net-(U11-VBST)") (class "Default")
      (node (ref "C103") (pin "2") (pinfunction "2_2") (pintype "passive"))
      (node (ref "U11") (pin "6") (pinfunction "VBST_6") (pintype "passive"))
    )
    (net (code "28") (name "Net-(U11-VFB)") (class "Default")
      (node (ref "R65") (pin "2") (pinfunction "2_2") (pintype "passive"))
      (node (ref "R67") (pin "1") (pinfunction "1_1") (pintype "passive"))
      (node (ref "U11") (pin "4") (pinfunction "VFB_4") (pintype "passive"))
    )
    (net (code "29") (name "Net-(U12-EN)") (class "Default")
      (node (ref "R71") (pin "1") (pinfunction "1_1") (pintype "passive"))
      (node (ref "U12") (pin "3") (pinfunction "EN_3") (pintype "passive"))
    )
    (net (code "30") (name "Net-(U13-BST)") (class "Default")
      (node (ref "C129") (pin "1") (pinfunction "1_1") (pintype "passive"))
      (node (ref "U13") (pin "1") (pinfunction "BST_1") (pintype "passive"))
    )
    (net (code "31") (name "Net-(U13-EN)") (class "Default")
      (node (ref "R95") (pin "1") (pinfunction "1_1") (pintype "passive"))
      (node (ref "R96") (pin "2") (pinfunction "2_2") (pintype "passive"))
      (node (ref "U13") (pin "12") (pinfunction "EN_12") (pintype "passive"))
    )
    (net (code "32") (name "Net-(U13-FB)") (class "Default")
      (node (ref "R72") (pin "2") (pinfunction "2_2") (pintype "passive"))
      (node (ref "R76") (pin "1") (pinfunction "1_1") (pintype "passive"))
      (node (ref "U13") (pin "14") (pinfunction "FB_14") (pintype "passive"))
    )
    (net (code "33") (name "Net-(U13-MODE)") (class "Default")
      (node (ref "R74") (pin "2") (pinfunction "2_2") (pintype "passive"))
      (node (ref "R75") (pin "2") (pinfunction "2_2") (pintype "passive"))
      (node (ref "U13") (pin "15") (pinfunction "MODE_15") (pintype "passive"))
    )
    (net (code "34") (name "Net-(U13-SS)") (class "Default")
      (node (ref "C134") (pin "2") (pinfunction "2_2") (pintype "passive"))
      (node (ref "U13") (pin "11") (pinfunction "SS_11") (pintype "passive"))
    )
    (net (code "35") (name "Net-(U13-VCC)") (class "Default")
      (node (ref "C135") (pin "2") (pinfunction "2_2") (pintype "passive"))
      (node (ref "R74") (pin "1") (pinfunction "1_1") (pintype "passive"))
      (node (ref "U13") (pin "17") (pinfunction "VCC_17") (pintype "passive"))
    )
    (net (code "36") (name "Net-(U14-EN)") (class "Default")
      (node (ref "R73") (pin "1") (pinfunction "1_1") (pintype "passive"))
      (node (ref "U14") (pin "3") (pinfunction "EN_3") (pintype "passive"))
    )
    (net (code "37") (name "Net-(U24-BST)") (class "Default")
      (node (ref "C148") (pin "1") (pinfunction "1_1") (pintype "passive"))
      (node (ref "U24") (pin "1") (pinfunction "BST_1") (pintype "passive"))
    )
    (net (code "38") (name "Net-(U24-EN)") (class "Default")
      (node (ref "R102") (pin "2") (pinfunction "2_2") (pintype "passive"))
      (node (ref "R98") (pin "1") (pinfunction "1_1") (pintype "passive"))
      (node (ref "U24") (pin "12") (pinfunction "EN_12") (pintype "passive"))
    )
    (net (code "39") (name "Net-(U24-FB)") (class "Default")
      (node (ref "R101") (pin "1") (pinfunction "1_1") (pintype "passive"))
      (node (ref "R97") (pin "2") (pinfunction "2_2") (pintype "passive"))
      (node (ref "U24") (pin "14") (pinfunction "FB_14") (pintype "passive"))
    )
    (net (code "40") (name "Net-(U24-MODE)") (class "Default")
      (node (ref "R100") (pin "2") (pinfunction "2_2") (pintype "passive"))
      (node (ref "R99") (pin "2") (pinfunction "2_2") (pintype "passive"))
      (node (ref "U24") (pin "15") (pinfunction "MODE_15") (pintype "passive"))
    )
    (net (code "41") (name "Net-(U24-SS)") (class "Default")
      (node (ref "C149") (pin "2") (pinfunction "2_2") (pintype "passive"))
      (node (ref "U24") (pin "11") (pinfunction "SS_11") (pintype "passive"))
    )
    (net (code "42") (name "Net-(U24-VCC)") (class "Default")
      (node (ref "C150") (pin "2") (pinfunction "2_2") (pintype "passive"))
      (node (ref "R99") (pin "1") (pinfunction "1_1") (pintype "passive"))
      (node (ref "U24") (pin "17") (pinfunction "VCC_17") (pintype "passive"))
    )
    (net (code "43") (name "VCC1.05V") (class "Default")
      (node (ref "C83") (pin "2") (pinfunction "2_2") (pintype "passive"))
      (node (ref "C84") (pin "2") (pinfunction "2_2") (pintype "passive"))
      (node (ref "C85") (pin "2") (pinfunction "2_2") (pintype "passive"))
      (node (ref "C86") (pin "2") (pinfunction "2_2") (pintype "passive"))
      (node (ref "E2") (pin "1") (pinfunction "A_1") (pintype "passive"))
      (node (ref "E3") (pin "1") (pinfunction "A_1") (pintype "passive"))
      (node (ref "L1") (pin "2") (pinfunction "2_2") (pintype "passive"))
      (node (ref "R58") (pin "1") (pinfunction "1_1") (pintype "passive"))
    )
    (net (code "44") (name "VCC1.8V") (class "Default")
      (node (ref "C106") (pin "2") (pinfunction "2_2") (pintype "passive"))
      (node (ref "C107") (pin "2") (pinfunction "2_2") (pintype "passive"))
      (node (ref "C108") (pin "2") (pinfunction "2_2") (pintype "passive"))
      (node (ref "C109") (pin "2") (pinfunction "2_2") (pintype "passive"))
      (node (ref "E7") (pin "1") (pinfunction "A_1") (pintype "passive"))
      (node (ref "E8") (pin "1") (pinfunction "A_1") (pintype "passive"))
      (node (ref "L4") (pin "2") (pinfunction "2_2") (pintype "passive"))
      (node (ref "R66") (pin "1") (pinfunction "1_1") (pintype "passive"))
    )
    (net (code "45") (name "VCC3.3V") (class "Default")
      (node (ref "C144") (pin "2") (pinfunction "2_2") (pintype "passive"))
      (node (ref "C145") (pin "2") (pinfunction "2_2") (pintype "passive"))
      (node (ref "C146") (pin "2") (pinfunction "2_2") (pintype "passive"))
      (node (ref "C147") (pin "2") (pinfunction "2_2") (pintype "passive"))
      (node (ref "E14") (pin "1") (pinfunction "A_1") (pintype "passive"))
      (node (ref "E15") (pin "1") (pinfunction "A_1") (pintype "passive"))
      (node (ref "L7") (pin "2") (pinfunction "2_2") (pintype "passive"))
      (node (ref "R97") (pin "1") (pinfunction "1_1") (pintype "passive"))
    )
    (net (code "46") (name "VCC3.3V-GPU1") (class "Default")
      (node (ref "C90") (pin "2") (pinfunction "2_2") (pintype "passive"))
      (node (ref "C91") (pin "2") (pinfunction "2_2") (pintype "passive"))
      (node (ref "C92") (pin "2") (pinfunction "2_2") (pintype "passive"))
      (node (ref "C93") (pin "2") (pinfunction "2_2") (pintype "passive"))
      (node (ref "E4") (pin "1") (pinfunction "A_1") (pintype "passive"))
      (node (ref "L2") (pin "2") (pinfunction "2_2") (pintype "passive"))
      (node (ref "R57") (pin "1") (pinfunction "1_1") (pintype "passive"))
    )
    (net (code "47") (name "VCC3.3V-GPU2") (class "Default")
      (node (ref "C100") (pin "2") (pinfunction "2_2") (pintype "passive"))
      (node (ref "C101") (pin "2") (pinfunction "2_2") (pintype "passive"))
      (node (ref "C102") (pin "2") (pinfunction "2_2") (pintype "passive"))
      (node (ref "C99") (pin "2") (pinfunction "2_2") (pintype "passive"))
      (node (ref "E5") (pin "1") (pinfunction "A_1") (pintype "passive"))
      (node (ref "L3") (pin "2") (pinfunction "2_2") (pintype "passive"))
      (node (ref "R63") (pin "1") (pinfunction "1_1") (pintype "passive"))
    )
    (net (code "48") (name "VCC3.3V-GPU3") (class "Default")
      (node (ref "C113") (pin "2") (pinfunction "2_2") (pintype "passive"))
      (node (ref "C114") (pin "2") (pinfunction "2_2") (pintype "passive"))
      (node (ref "C115") (pin "2") (pinfunction "2_2") (pintype "passive"))
      (node (ref "C116") (pin "2") (pinfunction "2_2") (pintype "passive"))
      (node (ref "E9") (pin "1") (pinfunction "A_1") (pintype "passive"))
      (node (ref "L5") (pin "2") (pinfunction "2_2") (pintype "passive"))
      (node (ref "R65") (pin "1") (pinfunction "1_1") (pintype "passive"))
    )
    (net (code "49") (name "VCC5.0V") (class "Default")
      (node (ref "C119") (pin "2") (pinfunction "2_2") (pintype "passive"))
      (node (ref "C120") (pin "1") (pinfunction "1_1") (pintype "passive"))
      (node (ref "C125") (pin "2") (pinfunction "2_2") (pintype "passive"))
      (node (ref "C126") (pin "2") (pinfunction "2_2") (pintype "passive"))
      (node (ref "C127") (pin "2") (pinfunction "2_2") (pintype "passive"))
      (node (ref "C128") (pin "2") (pinfunction "2_2") (pintype "passive"))
      (node (ref "C130") (pin "2") (pinfunction "2_2") (pintype "passive"))
      (node (ref "C131") (pin "1") (pinfunction "1_1") (pintype "passive"))
      (node (ref "E11") (pin "1") (pinfunction "A_1") (pintype "passive"))
      (node (ref "E12") (pin "1") (pinfunction "A_1") (pintype "passive"))
      (node (ref "L6") (pin "2") (pinfunction "2_2") (pintype "passive"))
      (node (ref "R71") (pin "2") (pinfunction "2_2") (pintype "passive"))
      (node (ref "R72") (pin "1") (pinfunction "1_1") (pintype "passive"))
      (node (ref "R73") (pin "2") (pinfunction "2_2") (pintype "passive"))
      (node (ref "U12") (pin "1") (pinfunction "VIN_1") (pintype "passive"))
      (node (ref "U14") (pin "1") (pinfunction "VIN_1") (pintype "passive"))
    )
    (net (code "50") (name "VCC12V") (class "Default")
      (node (ref "C104") (pin "2") (pinfunction "2_2") (pintype "passive"))
      (node (ref "C105") (pin "2") (pinfunction "2_2") (pintype "passive"))
      (node (ref "C110") (pin "2") (pinfunction "2_2") (pintype "passive"))
      (node (ref "C111") (pin "2") (pinfunction "2_2") (pintype "passive"))
      (node (ref "C123") (pin "2") (pinfunction "2_2") (pintype "passive"))
      (node (ref "C124") (pin "2") (pinfunction "2_2") (pintype "passive"))
      (node (ref "C142") (pin "2") (pinfunction "2_2") (pintype "passive"))
      (node (ref "C143") (pin "2") (pinfunction "2_2") (pintype "passive"))
      (node (ref "C81") (pin "2") (pinfunction "2_2") (pintype "passive"))
      (node (ref "C82") (pin "2") (pinfunction "2_2") (pintype "passive"))
      (node (ref "C87") (pin "2") (pinfunction "2_2") (pintype "passive"))
      (node (ref "C88") (pin "2") (pinfunction "2_2") (pintype "passive"))
      (node (ref "C97") (pin "2") (pinfunction "2_2") (pintype "passive"))
      (node (ref "C98") (pin "2") (pinfunction "2_2") (pintype "passive"))
      (node (ref "E1") (pin "1") (pinfunction "A_1") (pintype "passive"))
      (node (ref "E10") (pin "1") (pinfunction "A_1") (pintype "passive"))
      (node (ref "E13") (pin "1") (pinfunction "A_1") (pintype "passive"))
      (node (ref "E6") (pin "1") (pinfunction "A_1") (pintype "passive"))
      (node (ref "R92") (pin "1") (pinfunction "1_1") (pintype "passive"))
      (node (ref "R93") (pin "1") (pinfunction "1_1") (pintype "passive"))
      (node (ref "R94") (pin "1") (pinfunction "1_1") (pintype "passive"))
      (node (ref "R95") (pin "2") (pinfunction "2_2") (pintype "passive"))
      (node (ref "R98") (pin "2") (pinfunction "2_2") (pintype "passive"))
      (node (ref "U10") (pin "2") (pinfunction "VIN_2") (pintype "passive"))
      (node (ref "U10") (pin "3") (pinfunction "VIN_3") (pintype "passive"))
      (node (ref "U10") (pin "4") (pinfunction "VIN_4") (pintype "passive"))
      (node (ref "U10") (pin "5") (pinfunction "VIN_5") (pintype "passive"))
      (node (ref "U11") (pin "3") (pinfunction "VIN_3") (pintype "passive"))
      (node (ref "U13") (pin "2") (pinfunction "VIN_2") (pintype "passive"))
      (node (ref "U13") (pin "3") (pinfunction "VIN_3") (pintype "passive"))
      (node (ref "U13") (pin "4") (pinfunction "VIN_4") (pintype "passive"))
      (node (ref "U13") (pin "5") (pinfunction "VIN_5") (pintype "passive"))
      (node (ref "U24") (pin "2") (pinfunction "VIN_2") (pintype "passive"))
      (node (ref "U24") (pin "3") (pinfunction "VIN_3") (pintype "passive"))
      (node (ref "U24") (pin "4") (pinfunction "VIN_4") (pintype "passive"))
      (node (ref "U24") (pin "5") (pinfunction "VIN_5") (pintype "passive"))
      (node (ref "U7") (pin "2") (pinfunction "VIN_2") (pintype "passive"))
      (node (ref "U7") (pin "3") (pinfunction "VIN_3") (pintype "passive"))
      (node (ref "U7") (pin "4") (pinfunction "VIN_4") (pintype "passive"))
      (node (ref "U7") (pin "5") (pinfunction "VIN_5") (pintype "passive"))
      (node (ref "U8") (pin "3") (pinfunction "VIN_3") (pintype "passive"))
      (node (ref "U9") (pin "3") (pinfunction "VIN_3") (pintype "passive"))
    )
    (net (code "51") (name "VSUS1.05V") (class "Default")
      (node (ref "C121") (pin "2") (pinfunction "2_2") (pintype "passive"))
      (node (ref "C122") (pin "1") (pinfunction "1_1") (pintype "passive"))
      (node (ref "U12") (pin "5") (pinfunction "OUT_5") (pintype "passive"))
    )
    (net (code "52") (name "VSUS3.3V") (class "Default")
      (node (ref "C132") (pin "2") (pinfunction "2_2") (pintype "passive"))
      (node (ref "C133") (pin "1") (pinfunction "1_1") (pintype "passive"))
      (node (ref "U10") (pin "12") (pinfunction "EN_12") (pintype "passive"))
      (node (ref "U14") (pin "5") (pinfunction "OUT_5") (pintype "passive"))
      (node (ref "U7") (pin "12") (pinfunction "EN_12") (pintype "passive"))
    )
    (net (code "53") (name "unconnected-(U10-PGOOD-Pad9)") (class "Default")
      (node (ref "U10") (pin "9") (pinfunction "PGOOD_9") (pintype "passive+no_connect"))
    )
    (net (code "54") (name "unconnected-(U12-NC-Pad4)") (class "Default")
      (node (ref "U12") (pin "4") (pinfunction "NC_4") (pintype "passive+no_connect"))
    )
    (net (code "55") (name "unconnected-(U13-PGOOD-Pad9)") (class "Default")
      (node (ref "U13") (pin "9") (pinfunction "PGOOD_9") (pintype "passive+no_connect"))
    )
    (net (code "56") (name "unconnected-(U14-NC-Pad4)") (class "Default")
      (node (ref "U14") (pin "4") (pinfunction "NC_4") (pintype "passive+no_connect"))
    )
    (net (code "57") (name "unconnected-(U24-PGOOD-Pad9)") (class "Default")
      (node (ref "U24") (pin "9") (pinfunction "PGOOD_9") (pintype "passive+no_connect"))
    )
  )
)
